# Reset.net
KiCad netlist of a schematic drawn in Altium Designer
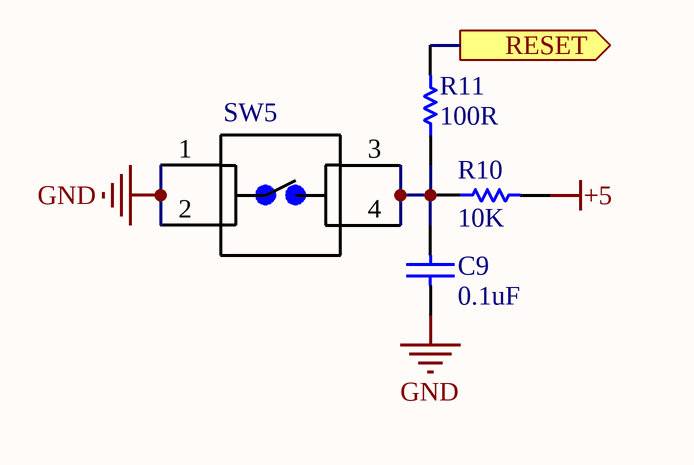
[diagram p0: Reset.SchDoc]

(export (version "E")
  (design (tool "Eeschema 10.0.6"))
  (components
    (comp (ref "C9")
      (value "0.1uF")
      (footprint "CAPC2013X94X50LL20T25")
      (description "Chip Capacitor, 0.1 uF, +/- 5%, 50 V, -55 to 125 degC, 0805 (2012 Metric), RoHS, Tape and Reel")
      (fields (field (name "TOLERANCE") "5%") (field (name "MANUFACTURER") "AVX"))
      (libsource (lib "Altium Content Vault") (part "CAP-NP-2"))
    )
    (comp (ref "R10")
      (value "10K")
      (footprint "RESC0805(2012)_L")
      (description "10K2 0.125W 1% 0805 (2012 Metric)  SMD")
      (fields (field (name "TOLERANCE") "1 %") (field (name "POWER") "0.125 W"))
      (libsource (lib "Altium Content Vault") (part "RES"))
    )
    (comp (ref "R11")
      (value "100R")
      (footprint "RESC0805(2012)_L")
      (description "100R 0.125W 1% 0805 (2012 Metric)  SMD")
      (fields (field (name "POWER") "0.125 W") (field (name "TOLERANCE") "1 %"))
      (libsource (lib "Altium Content Vault") (part "RES"))
    )
    (comp (ref "SW5")
      (value "1825910-7")
      (footprint "Switch 6mm 24V (NO)")
      (description "FSM4JAH=6MM TACT SWITCH, HIGH TEMP")
      (fields (field (name "MF") "TE Connectivity") (field (name "DIGI-KEY_PART_NUMBER") "450-1804-ND"))
      (libsource (lib "Husky Robotics Standard Library 2019-2020") (part "Switch 6mm 24V (NO)"))
    )
  )
  (nets
    (net (code "1") (name "+5") (class "Default")
      (node (ref "R10") (pin "2") (pinfunction "2_2") (pintype "passive"))
    )
    (net (code "2") (name "/RESET") (class "Default")
      (node (ref "R11") (pin "2") (pinfunction "2_2") (pintype "passive"))
    )
    (net (code "3") (name "GND") (class "Default")
      (node (ref "C9") (pin "1") (pinfunction "1_1") (pintype "passive"))
      (node (ref "SW5") (pin "1") (pinfunction "1_1") (pintype "passive"))
      (node (ref "SW5") (pin "2") (pinfunction "2_2") (pintype "passive"))
    )
    (net (code "4") (name "Net-(C9-Pad2)") (class "Default")
      (node (ref "C9") (pin "2") (pinfunction "2_2") (pintype "passive"))
      (node (ref "R10") (pin "1") (pinfunction "1_1") (pintype "passive"))
      (node (ref "R11") (pin "1") (pinfunction "1_1") (pintype "passive"))
      (node (ref "SW5") (pin "3") (pinfunction "3_3") (pintype "passive"))
      (node (ref "SW5") (pin "4") (pinfunction "4_4") (pintype "passive"))
    )
  )
)
